# dtb219-schematic.net
KiCad netlist of a schematic drawn in Altium Designer
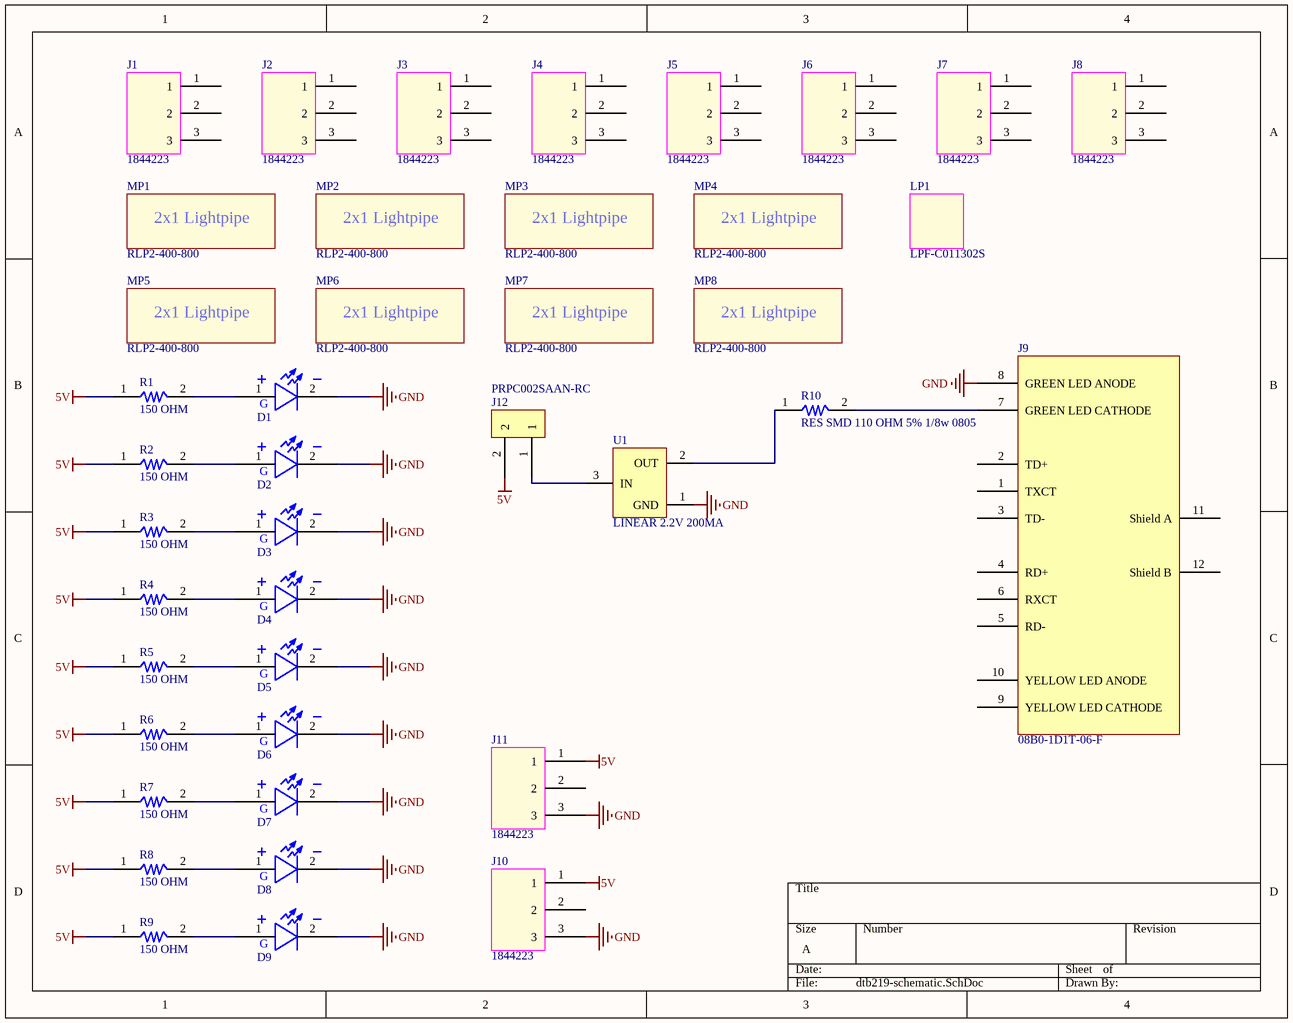
[diagram p0: dtb219-schematic.SchDoc]

(export (version "E")
  (design (tool "Eeschema 10.0.6"))
  (components
    (comp (ref "D1")
      (value "Green LED Clear SMD")
      (footprint "LTST-C19X")
      (description "Green 571nm LED Indication - Discrete 2V 0603 (1608 Metric)")
      (fields (field (name "MANUFACTURER") "Lite-On Inc."))
      (libsource (lib "andre-altium-lib") (part "LED Green"))
    )
    (comp (ref "D2")
      (value "Green LED Clear SMD")
      (footprint "LTST-C19X")
      (description "Green 571nm LED Indication - Discrete 2V 0603 (1608 Metric)")
      (fields (field (name "MANUFACTURER") "Lite-On Inc."))
      (libsource (lib "andre-altium-lib") (part "LED Green"))
    )
    (comp (ref "D3")
      (value "Green LED Clear SMD")
      (footprint "LTST-C19X")
      (description "Green 571nm LED Indication - Discrete 2V 0603 (1608 Metric)")
      (fields (field (name "MANUFACTURER") "Lite-On Inc."))
      (libsource (lib "andre-altium-lib") (part "LED Green"))
    )
    (comp (ref "D4")
      (value "Green LED Clear SMD")
      (footprint "LTST-C19X")
      (description "Green 571nm LED Indication - Discrete 2V 0603 (1608 Metric)")
      (fields (field (name "MANUFACTURER") "Lite-On Inc."))
      (libsource (lib "andre-altium-lib") (part "LED Green"))
    )
    (comp (ref "D5")
      (value "Green LED Clear SMD")
      (footprint "LTST-C19X")
      (description "Green 571nm LED Indication - Discrete 2V 0603 (1608 Metric)")
      (fields (field (name "MANUFACTURER") "Lite-On Inc."))
      (libsource (lib "andre-altium-lib") (part "LED Green"))
    )
    (comp (ref "D6")
      (value "Green LED Clear SMD")
      (footprint "LTST-C19X")
      (description "Green 571nm LED Indication - Discrete 2V 0603 (1608 Metric)")
      (fields (field (name "MANUFACTURER") "Lite-On Inc."))
      (libsource (lib "andre-altium-lib") (part "LED Green"))
    )
    (comp (ref "D7")
      (value "Green LED Clear SMD")
      (footprint "LTST-C19X")
      (description "Green 571nm LED Indication - Discrete 2V 0603 (1608 Metric)")
      (fields (field (name "MANUFACTURER") "Lite-On Inc."))
      (libsource (lib "andre-altium-lib") (part "LED Green"))
    )
    (comp (ref "D8")
      (value "Green LED Clear SMD")
      (footprint "LTST-C19X")
      (description "Green 571nm LED Indication - Discrete 2V 0603 (1608 Metric)")
      (fields (field (name "MANUFACTURER") "Lite-On Inc."))
      (libsource (lib "andre-altium-lib") (part "LED Green"))
    )
    (comp (ref "D9")
      (value "Green LED Clear SMD")
      (footprint "LTST-C19X")
      (description "Green 571nm LED Indication - Discrete 2V 0603 (1608 Metric)")
      (fields (field (name "MANUFACTURER") "Lite-On Inc."))
      (libsource (lib "andre-altium-lib") (part "LED Green"))
    )
    (comp (ref "J1")
      (value "1844223")
      (footprint "1844223")
      (fields (field (name "MANUFACTURER") "Phoenix Contact"))
      (libsource (lib "Allen_Integrated_Library") (part "1844223"))
    )
    (comp (ref "J2")
      (value "1844223")
      (footprint "1844223")
      (fields (field (name "MANUFACTURER") "Phoenix Contact"))
      (libsource (lib "Allen_Integrated_Library") (part "1844223"))
    )
    (comp (ref "J3")
      (value "1844223")
      (footprint "1844223")
      (fields (field (name "MANUFACTURER") "Phoenix Contact"))
      (libsource (lib "Allen_Integrated_Library") (part "1844223"))
    )
    (comp (ref "J4")
      (value "1844223")
      (footprint "1844223")
      (fields (field (name "MANUFACTURER") "Phoenix Contact"))
      (libsource (lib "Allen_Integrated_Library") (part "1844223"))
    )
    (comp (ref "J5")
      (value "1844223")
      (footprint "1844223")
      (fields (field (name "MANUFACTURER") "Phoenix Contact"))
      (libsource (lib "Allen_Integrated_Library") (part "1844223"))
    )
    (comp (ref "J6")
      (value "1844223")
      (footprint "1844223")
      (fields (field (name "MANUFACTURER") "Phoenix Contact"))
      (libsource (lib "Allen_Integrated_Library") (part "1844223"))
    )
    (comp (ref "J7")
      (value "1844223")
      (footprint "1844223")
      (fields (field (name "MANUFACTURER") "Phoenix Contact"))
      (libsource (lib "Allen_Integrated_Library") (part "1844223"))
    )
    (comp (ref "J8")
      (value "1844223")
      (footprint "1844223")
      (fields (field (name "MANUFACTURER") "Phoenix Contact"))
      (libsource (lib "Allen_Integrated_Library") (part "1844223"))
    )
    (comp (ref "J9")
      (value "08B0-1D1T-06-F")
      (footprint "08B0-1D1T-06-F")
      (description "CONN MAGJACK 1PORT 100 BASE-T")
      (fields (field (name "MANUFACTURER") "Bel Fuse Inc"))
      (libsource (lib "VoltServer Library") (part "08B0-1D1T-06-F"))
    )
    (comp (ref "J10")
      (value "1844223")
      (footprint "1844223")
      (fields (field (name "MANUFACTURER") "Phoenix Contact"))
      (libsource (lib "Allen_Integrated_Library") (part "1844223"))
    )
    (comp (ref "J11")
      (value "1844223")
      (footprint "1844223")
      (fields (field (name "MANUFACTURER") "Phoenix Contact"))
      (libsource (lib "Allen_Integrated_Library") (part "1844223"))
    )
    (comp (ref "J12")
      (value "PRPC002SAAN-RC")
      (footprint "PRPC002SAAN-RC")
      (description "CONN HEADER .100\" SNGL STR 2POS")
      (fields (field (name "MANUFACTURER") "Sullins Connector Solutions"))
      (libsource (lib "Allen_Integrated_Library") (part "PRPC002SAAN-RC"))
    )
    (comp (ref "LP1")
      (value "LPF-C011302S")
      (footprint "LPF-C011302S")
      (description "Light Pipe Single Clear Rigid Round with Flat Top, 3mm Board Mount, Press Fit, Right Angle")
      (fields (field (name "MANUFACTURER") "Lumex Opto/Components Inc."))
      (libsource (lib "Allen_Integrated_Library") (part "LPF-C011302S"))
    )
    (comp (ref "MP1")
      (value "RLP2-400-800")
      (footprint "RLP2-400-800")
      (description "Light Pipe 2 Wide Clear Rigid Round with Flat Top, 2.8mm Board Mount, Snap-In, Right Angle")
      (fields (field (name "MANUFACTURER") "Bivar"))
      (libsource (lib "VoltServer Library") (part "RLP2-400-800"))
    )
    (comp (ref "MP2")
      (value "RLP2-400-800")
      (footprint "RLP2-400-800")
      (description "Light Pipe 2 Wide Clear Rigid Round with Flat Top, 2.8mm Board Mount, Snap-In, Right Angle")
      (fields (field (name "MANUFACTURER") "Bivar"))
      (libsource (lib "VoltServer Library") (part "RLP2-400-800"))
    )
    (comp (ref "MP3")
      (value "RLP2-400-800")
      (footprint "RLP2-400-800")
      (description "Light Pipe 2 Wide Clear Rigid Round with Flat Top, 2.8mm Board Mount, Snap-In, Right Angle")
      (fields (field (name "MANUFACTURER") "Bivar"))
      (libsource (lib "VoltServer Library") (part "RLP2-400-800"))
    )
    (comp (ref "MP4")
      (value "RLP2-400-800")
      (footprint "RLP2-400-800")
      (description "Light Pipe 2 Wide Clear Rigid Round with Flat Top, 2.8mm Board Mount, Snap-In, Right Angle")
      (fields (field (name "MANUFACTURER") "Bivar"))
      (libsource (lib "VoltServer Library") (part "RLP2-400-800"))
    )
    (comp (ref "MP5")
      (value "RLP2-400-800")
      (footprint "RLP2-400-800")
      (description "Light Pipe 2 Wide Clear Rigid Round with Flat Top, 2.8mm Board Mount, Snap-In, Right Angle")
      (fields (field (name "MANUFACTURER") "Bivar"))
      (libsource (lib "VoltServer Library") (part "RLP2-400-800"))
    )
    (comp (ref "MP6")
      (value "RLP2-400-800")
      (footprint "RLP2-400-800")
      (description "Light Pipe 2 Wide Clear Rigid Round with Flat Top, 2.8mm Board Mount, Snap-In, Right Angle")
      (fields (field (name "MANUFACTURER") "Bivar"))
      (libsource (lib "VoltServer Library") (part "RLP2-400-800"))
    )
    (comp (ref "MP7")
      (value "RLP2-400-800")
      (footprint "RLP2-400-800")
      (description "Light Pipe 2 Wide Clear Rigid Round with Flat Top, 2.8mm Board Mount, Snap-In, Right Angle")
      (fields (field (name "MANUFACTURER") "Bivar"))
      (libsource (lib "VoltServer Library") (part "RLP2-400-800"))
    )
    (comp (ref "MP8")
      (value "RLP2-400-800")
      (footprint "RLP2-400-800")
      (description "Light Pipe 2 Wide Clear Rigid Round with Flat Top, 2.8mm Board Mount, Snap-In, Right Angle")
      (fields (field (name "MANUFACTURER") "Bivar"))
      (libsource (lib "VoltServer Library") (part "RLP2-400-800"))
    )
    (comp (ref "R1")
      (value "150 OHM")
      (footprint "0805 Footprint")
      (description "150 Ohms ±5% 0.5W, 1/2W Chip Resistor 0805 (2012 Metric)")
      (fields (field (name "MANUFACTURER") "Panasonic Electionic Components"))
      (libsource (lib "andre-altium-lib") (part "ERJ-P06J151V"))
    )
    (comp (ref "R2")
      (value "150 OHM")
      (footprint "0805 Footprint")
      (description "150 Ohms ±5% 0.5W, 1/2W Chip Resistor 0805 (2012 Metric)")
      (fields (field (name "MANUFACTURER") "Panasonic Electionic Components"))
      (libsource (lib "andre-altium-lib") (part "ERJ-P06J151V"))
    )
    (comp (ref "R3")
      (value "150 OHM")
      (footprint "0805 Footprint")
      (description "150 Ohms ±5% 0.5W, 1/2W Chip Resistor 0805 (2012 Metric)")
      (fields (field (name "MANUFACTURER") "Panasonic Electionic Components"))
      (libsource (lib "andre-altium-lib") (part "ERJ-P06J151V"))
    )
    (comp (ref "R4")
      (value "150 OHM")
      (footprint "0805 Footprint")
      (description "150 Ohms ±5% 0.5W, 1/2W Chip Resistor 0805 (2012 Metric)")
      (fields (field (name "MANUFACTURER") "Panasonic Electionic Components"))
      (libsource (lib "andre-altium-lib") (part "ERJ-P06J151V"))
    )
    (comp (ref "R5")
      (value "150 OHM")
      (footprint "0805 Footprint")
      (description "150 Ohms ±5% 0.5W, 1/2W Chip Resistor 0805 (2012 Metric)")
      (fields (field (name "MANUFACTURER") "Panasonic Electionic Components"))
      (libsource (lib "andre-altium-lib") (part "ERJ-P06J151V"))
    )
    (comp (ref "R6")
      (value "150 OHM")
      (footprint "0805 Footprint")
      (description "150 Ohms ±5% 0.5W, 1/2W Chip Resistor 0805 (2012 Metric)")
      (fields (field (name "MANUFACTURER") "Panasonic Electionic Components"))
      (libsource (lib "andre-altium-lib") (part "ERJ-P06J151V"))
    )
    (comp (ref "R7")
      (value "150 OHM")
      (footprint "0805 Footprint")
      (description "150 Ohms ±5% 0.5W, 1/2W Chip Resistor 0805 (2012 Metric)")
      (fields (field (name "MANUFACTURER") "Panasonic Electionic Components"))
      (libsource (lib "andre-altium-lib") (part "ERJ-P06J151V"))
    )
    (comp (ref "R8")
      (value "150 OHM")
      (footprint "0805 Footprint")
      (description "150 Ohms ±5% 0.5W, 1/2W Chip Resistor 0805 (2012 Metric)")
      (fields (field (name "MANUFACTURER") "Panasonic Electionic Components"))
      (libsource (lib "andre-altium-lib") (part "ERJ-P06J151V"))
    )
    (comp (ref "R9")
      (value "150 OHM")
      (footprint "0805 Footprint")
      (description "150 Ohms ±5% 0.5W, 1/2W Chip Resistor 0805 (2012 Metric)")
      (fields (field (name "MANUFACTURER") "Panasonic Electionic Components"))
      (libsource (lib "andre-altium-lib") (part "ERJ-P06J151V"))
    )
    (comp (ref "R10")
      (value "RES SMD 110 OHM 5% 1/8w 0805")
      (footprint "0805 Footprint")
      (description "110 Ohms ±5% 0.125W, 1/8W Chip Resistor 0805 (2012 Metric) Automotive AEC-Q200 Thick Film")
      (fields (field (name "MANUFACTURER") "Panasonic Electionic Components"))
      (libsource (lib "andre-altium-lib") (part "ERJ-6GEYJ111V"))
    )
    (comp (ref "U1")
      (value "LINEAR 2.2V 200MA")
      (footprint "SOT23-3")
      (description "Linear Voltage Regulator IC Positive Fixed 1 Output 200mA SOT-23-3")
      (fields (field (name "MANUFACTURER") "Texas Instruments"))
      (libsource (lib "andre-altium-lib") (part "TPS7A0522PDBZR"))
    )
  )
  (nets
    (net (code "1") (name "5V") (class "Default")
      (node (ref "J10") (pin "1") (pinfunction "1_1") (pintype "passive"))
      (node (ref "J11") (pin "1") (pinfunction "1_1") (pintype "passive"))
      (node (ref "J12") (pin "2") (pinfunction "2_2") (pintype "passive"))
      (node (ref "R1") (pin "1") (pinfunction "1_1") (pintype "passive"))
      (node (ref "R2") (pin "1") (pinfunction "1_1") (pintype "passive"))
      (node (ref "R3") (pin "1") (pinfunction "1_1") (pintype "passive"))
      (node (ref "R4") (pin "1") (pinfunction "1_1") (pintype "passive"))
      (node (ref "R5") (pin "1") (pinfunction "1_1") (pintype "passive"))
      (node (ref "R6") (pin "1") (pinfunction "1_1") (pintype "passive"))
      (node (ref "R7") (pin "1") (pinfunction "1_1") (pintype "passive"))
      (node (ref "R8") (pin "1") (pinfunction "1_1") (pintype "passive"))
      (node (ref "R9") (pin "1") (pinfunction "1_1") (pintype "passive"))
    )
    (net (code "2") (name "GND") (class "Default")
      (node (ref "D1") (pin "2") (pintype "passive"))
      (node (ref "D2") (pin "2") (pintype "passive"))
      (node (ref "D3") (pin "2") (pintype "passive"))
      (node (ref "D4") (pin "2") (pintype "passive"))
      (node (ref "D5") (pin "2") (pintype "passive"))
      (node (ref "D6") (pin "2") (pintype "passive"))
      (node (ref "D7") (pin "2") (pintype "passive"))
      (node (ref "D8") (pin "2") (pintype "passive"))
      (node (ref "D9") (pin "2") (pintype "passive"))
      (node (ref "J10") (pin "3") (pinfunction "3_3") (pintype "passive"))
      (node (ref "J11") (pin "3") (pinfunction "3_3") (pintype "passive"))
      (node (ref "J9") (pin "8") (pinfunction "GREEN_LED_ANODE_8") (pintype "passive"))
      (node (ref "U1") (pin "1") (pinfunction "GND_1") (pintype "passive"))
    )
    (net (code "3") (name "Net-(D1-Pad1)") (class "Default")
      (node (ref "D1") (pin "1") (pintype "passive"))
      (node (ref "R1") (pin "2") (pinfunction "2_2") (pintype "passive"))
    )
    (net (code "4") (name "Net-(D2-Pad1)") (class "Default")
      (node (ref "D2") (pin "1") (pintype "passive"))
      (node (ref "R2") (pin "2") (pinfunction "2_2") (pintype "passive"))
    )
    (net (code "5") (name "Net-(D3-Pad1)") (class "Default")
      (node (ref "D3") (pin "1") (pintype "passive"))
      (node (ref "R3") (pin "2") (pinfunction "2_2") (pintype "passive"))
    )
    (net (code "6") (name "Net-(D4-Pad1)") (class "Default")
      (node (ref "D4") (pin "1") (pintype "passive"))
      (node (ref "R4") (pin "2") (pinfunction "2_2") (pintype "passive"))
    )
    (net (code "7") (name "Net-(D5-Pad1)") (class "Default")
      (node (ref "D5") (pin "1") (pintype "passive"))
      (node (ref "R5") (pin "2") (pinfunction "2_2") (pintype "passive"))
    )
    (net (code "8") (name "Net-(D6-Pad1)") (class "Default")
      (node (ref "D6") (pin "1") (pintype "passive"))
      (node (ref "R6") (pin "2") (pinfunction "2_2") (pintype "passive"))
    )
    (net (code "9") (name "Net-(D7-Pad1)") (class "Default")
      (node (ref "D7") (pin "1") (pintype "passive"))
      (node (ref "R7") (pin "2") (pinfunction "2_2") (pintype "passive"))
    )
    (net (code "10") (name "Net-(D8-Pad1)") (class "Default")
      (node (ref "D8") (pin "1") (pintype "passive"))
      (node (ref "R8") (pin "2") (pinfunction "2_2") (pintype "passive"))
    )
    (net (code "11") (name "Net-(D9-Pad1)") (class "Default")
      (node (ref "D9") (pin "1") (pintype "passive"))
      (node (ref "R9") (pin "2") (pinfunction "2_2") (pintype "passive"))
    )
    (net (code "12") (name "Net-(J9-GREEN_LED_CATHODE)") (class "Default")
      (node (ref "J9") (pin "7") (pinfunction "GREEN_LED_CATHODE_7") (pintype "passive"))
      (node (ref "R10") (pin "2") (pinfunction "2_2") (pintype "passive"))
    )
    (net (code "13") (name "Net-(U1-IN)") (class "Default")
      (node (ref "J12") (pin "1") (pinfunction "1_1") (pintype "passive"))
      (node (ref "U1") (pin "3") (pinfunction "IN_3") (pintype "passive"))
    )
    (net (code "14") (name "Net-(U1-OUT)") (class "Default")
      (node (ref "R10") (pin "1") (pinfunction "1_1") (pintype "passive"))
      (node (ref "U1") (pin "2") (pinfunction "OUT_2") (pintype "passive"))
    )
    (net (code "15") (name "unconnected-(J1-Pad1)") (class "Default")
      (node (ref "J1") (pin "1") (pinfunction "1_1") (pintype "passive"))
    )
    (net (code "16") (name "unconnected-(J1-Pad2)") (class "Default")
      (node (ref "J1") (pin "2") (pinfunction "2_2") (pintype "passive"))
    )
    (net (code "17") (name "unconnected-(J1-Pad3)") (class "Default")
      (node (ref "J1") (pin "3") (pinfunction "3_3") (pintype "passive"))
    )
    (net (code "18") (name "unconnected-(J2-Pad1)") (class "Default")
      (node (ref "J2") (pin "1") (pinfunction "1_1") (pintype "passive"))
    )
    (net (code "19") (name "unconnected-(J2-Pad2)") (class "Default")
      (node (ref "J2") (pin "2") (pinfunction "2_2") (pintype "passive"))
    )
    (net (code "20") (name "unconnected-(J2-Pad3)") (class "Default")
      (node (ref "J2") (pin "3") (pinfunction "3_3") (pintype "passive"))
    )
    (net (code "21") (name "unconnected-(J3-Pad1)") (class "Default")
      (node (ref "J3") (pin "1") (pinfunction "1_1") (pintype "passive"))
    )
    (net (code "22") (name "unconnected-(J3-Pad2)") (class "Default")
      (node (ref "J3") (pin "2") (pinfunction "2_2") (pintype "passive"))
    )
    (net (code "23") (name "unconnected-(J3-Pad3)") (class "Default")
      (node (ref "J3") (pin "3") (pinfunction "3_3") (pintype "passive"))
    )
    (net (code "24") (name "unconnected-(J4-Pad1)") (class "Default")
      (node (ref "J4") (pin "1") (pinfunction "1_1") (pintype "passive"))
    )
    (net (code "25") (name "unconnected-(J4-Pad2)") (class "Default")
      (node (ref "J4") (pin "2") (pinfunction "2_2") (pintype "passive"))
    )
    (net (code "26") (name "unconnected-(J4-Pad3)") (class "Default")
      (node (ref "J4") (pin "3") (pinfunction "3_3") (pintype "passive"))
    )
    (net (code "27") (name "unconnected-(J5-Pad1)") (class "Default")
      (node (ref "J5") (pin "1") (pinfunction "1_1") (pintype "passive"))
    )
    (net (code "28") (name "unconnected-(J5-Pad2)") (class "Default")
      (node (ref "J5") (pin "2") (pinfunction "2_2") (pintype "passive"))
    )
    (net (code "29") (name "unconnected-(J5-Pad3)") (class "Default")
      (node (ref "J5") (pin "3") (pinfunction "3_3") (pintype "passive"))
    )
    (net (code "30") (name "unconnected-(J6-Pad1)") (class "Default")
      (node (ref "J6") (pin "1") (pinfunction "1_1") (pintype "passive"))
    )
    (net (code "31") (name "unconnected-(J6-Pad2)") (class "Default")
      (node (ref "J6") (pin "2") (pinfunction "2_2") (pintype "passive"))
    )
    (net (code "32") (name "unconnected-(J6-Pad3)") (class "Default")
      (node (ref "J6") (pin "3") (pinfunction "3_3") (pintype "passive"))
    )
    (net (code "33") (name "unconnected-(J7-Pad1)") (class "Default")
      (node (ref "J7") (pin "1") (pinfunction "1_1") (pintype "passive"))
    )
    (net (code "34") (name "unconnected-(J7-Pad2)") (class "Default")
      (node (ref "J7") (pin "2") (pinfunction "2_2") (pintype "passive"))
    )
    (net (code "35") (name "unconnected-(J7-Pad3)") (class "Default")
      (node (ref "J7") (pin "3") (pinfunction "3_3") (pintype "passive"))
    )
    (net (code "36") (name "unconnected-(J8-Pad1)") (class "Default")
      (node (ref "J8") (pin "1") (pinfunction "1_1") (pintype "passive"))
    )
    (net (code "37") (name "unconnected-(J8-Pad2)") (class "Default")
      (node (ref "J8") (pin "2") (pinfunction "2_2") (pintype "passive"))
    )
    (net (code "38") (name "unconnected-(J8-Pad3)") (class "Default")
      (node (ref "J8") (pin "3") (pinfunction "3_3") (pintype "passive"))
    )
    (net (code "39") (name "unconnected-(J9-RD+-Pad4)") (class "Default")
      (node (ref "J9") (pin "4") (pinfunction "RD+_4") (pintype "passive"))
    )
    (net (code "40") (name "unconnected-(J9-RD--Pad5)") (class "Default")
      (node (ref "J9") (pin "5") (pinfunction "RD-_5") (pintype "passive"))
    )
    (net (code "41") (name "unconnected-(J9-RXCT-Pad6)") (class "Default")
      (node (ref "J9") (pin "6") (pinfunction "RXCT_6") (pintype "passive"))
    )
    (net (code "42") (name "unconnected-(J9-Shield_A-Pad11)") (class "Default")
      (node (ref "J9") (pin "11") (pinfunction "Shield_A_11") (pintype "passive"))
    )
    (net (code "43") (name "unconnected-(J9-Shield_B-Pad12)") (class "Default")
      (node (ref "J9") (pin "12") (pinfunction "Shield_B_12") (pintype "passive"))
    )
    (net (code "44") (name "unconnected-(J9-TD+-Pad2)") (class "Default")
      (node (ref "J9") (pin "2") (pinfunction "TD+_2") (pintype "passive"))
    )
    (net (code "45") (name "unconnected-(J9-TD--Pad3)") (class "Default")
      (node (ref "J9") (pin "3") (pinfunction "TD-_3") (pintype "passive"))
    )
    (net (code "46") (name "unconnected-(J9-TXCT-Pad1)") (class "Default")
      (node (ref "J9") (pin "1") (pinfunction "TXCT_1") (pintype "passive"))
    )
    (net (code "47") (name "unconnected-(J9-YELLOW_LED_ANODE-Pad10)") (class "Default")
      (node (ref "J9") (pin "10") (pinfunction "YELLOW_LED_ANODE_10") (pintype "passive"))
    )
    (net (code "48") (name "unconnected-(J9-YELLOW_LED_CATHODE-Pad9)") (class "Default")
      (node (ref "J9") (pin "9") (pinfunction "YELLOW_LED_CATHODE_9") (pintype "passive"))
    )
    (net (code "49") (name "unconnected-(J10-Pad2)") (class "Default")
      (node (ref "J10") (pin "2") (pinfunction "2_2") (pintype "passive"))
    )
    (net (code "50") (name "unconnected-(J11-Pad2)") (class "Default")
      (node (ref "J11") (pin "2") (pinfunction "2_2") (pintype "passive"))
    )
  )
)
